# BBMiniPCB5x10.net
KiCad netlist of a schematic drawn in EAGLE
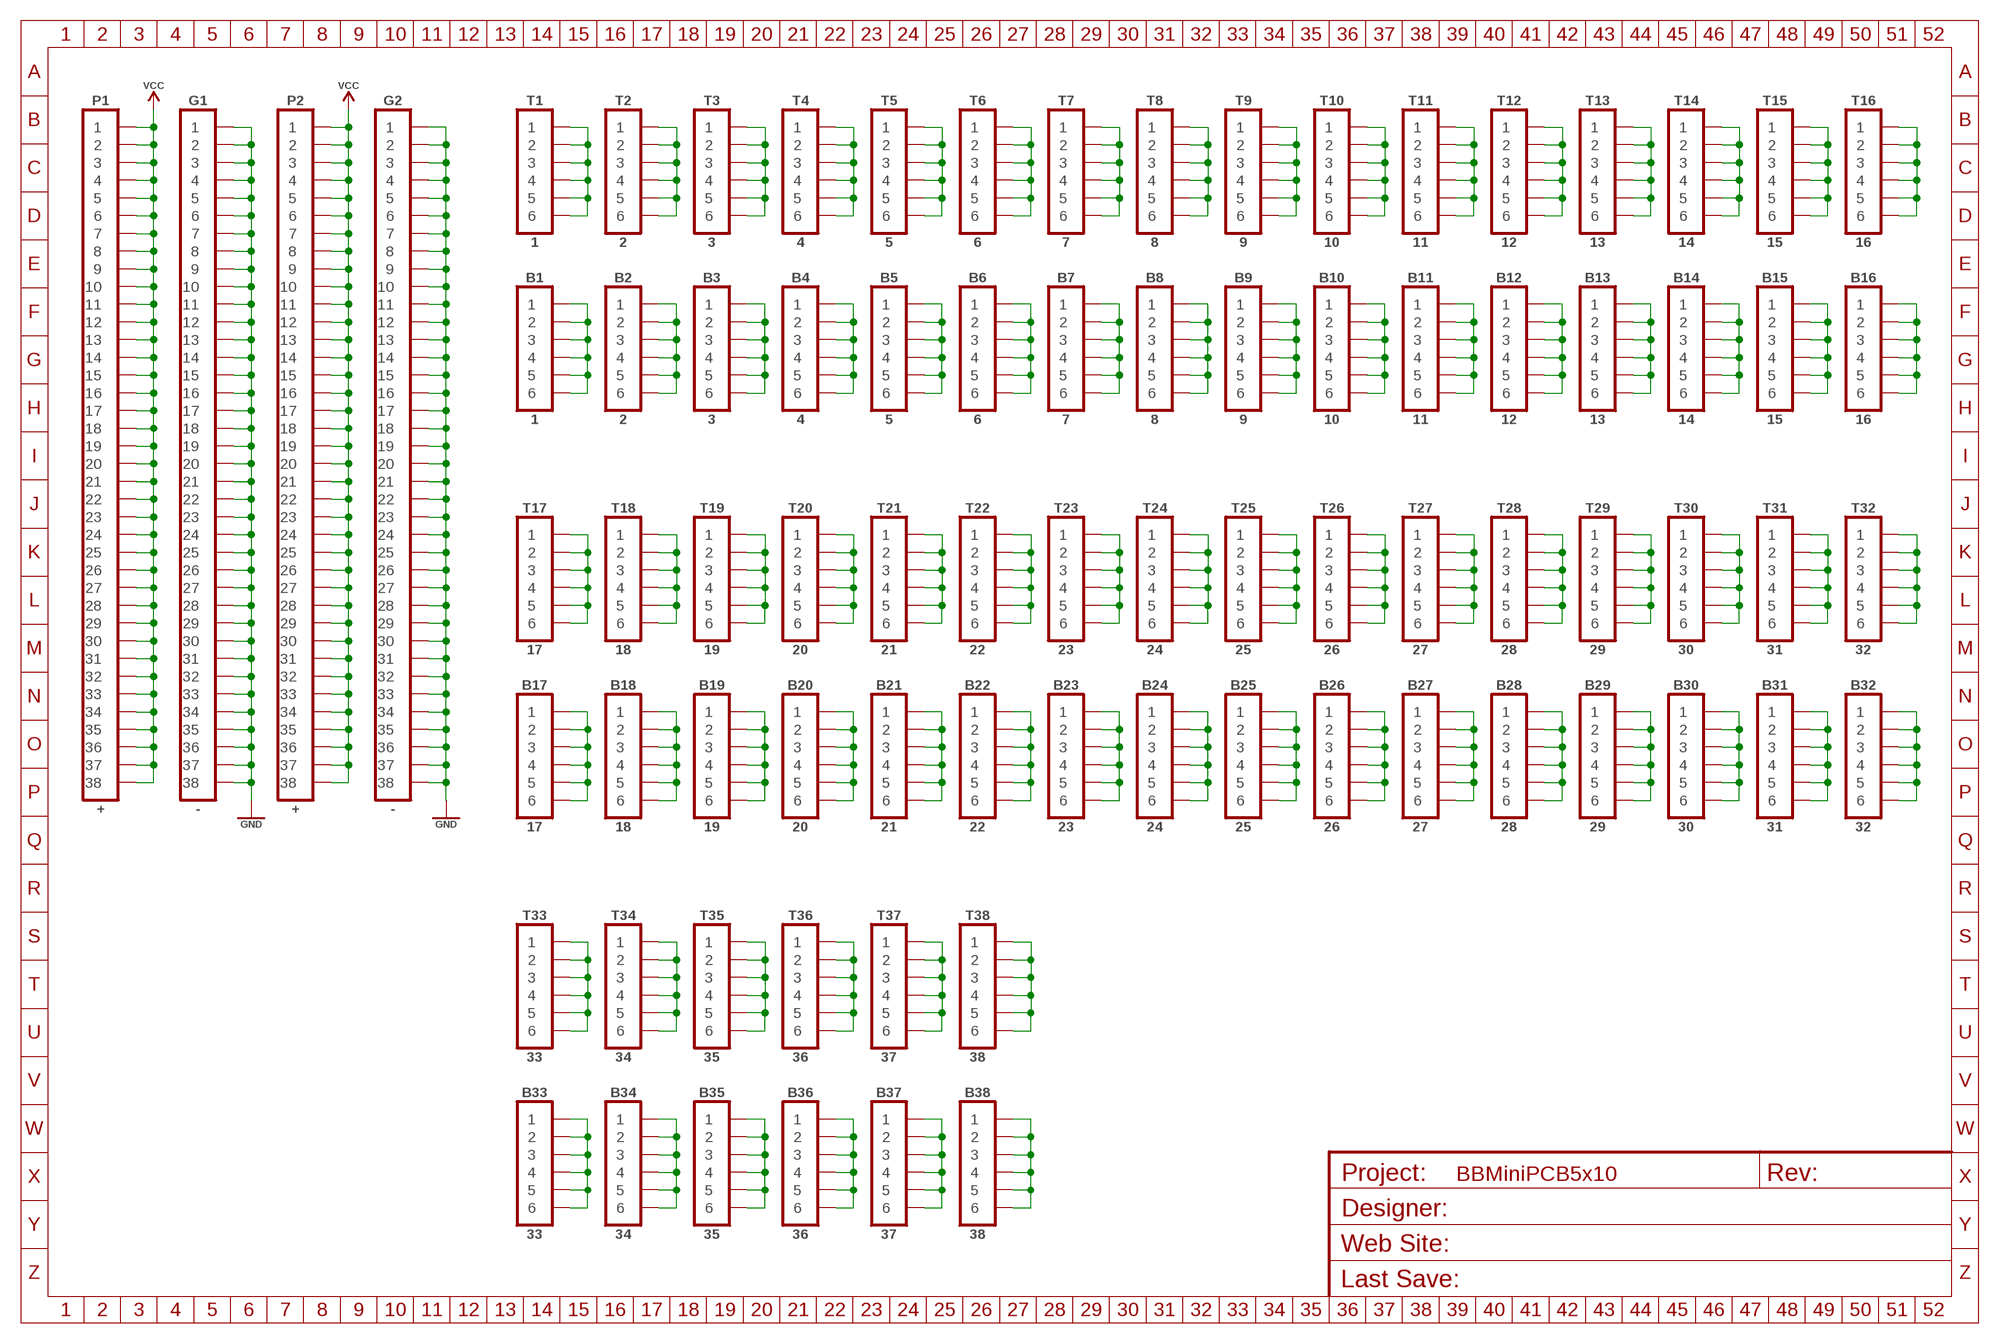
[diagram p0: schematic, sheet 1]

(export (version "E")
  (design (tool "Eeschema 10.0.6"))
  (components
    (comp (ref "B1")
      (value "1")
      (footprint "eagle-import:HDR_1X06_NOSILK")
      (libsource (lib "eagle-import") (part "HDR_1X06_NOSILK"))
    )
    (comp (ref "B2")
      (value "2")
      (footprint "eagle-import:HDR_1X06_NOSILK")
      (libsource (lib "eagle-import") (part "HDR_1X06_NOSILK"))
    )
    (comp (ref "B3")
      (value "3")
      (footprint "eagle-import:HDR_1X06_NOSILK")
      (libsource (lib "eagle-import") (part "HDR_1X06_NOSILK"))
    )
    (comp (ref "B4")
      (value "4")
      (footprint "eagle-import:HDR_1X06_NOSILK")
      (libsource (lib "eagle-import") (part "HDR_1X06_NOSILK"))
    )
    (comp (ref "B5")
      (value "5")
      (footprint "eagle-import:HDR_1X06_NOSILK")
      (libsource (lib "eagle-import") (part "HDR_1X06_NOSILK"))
    )
    (comp (ref "B6")
      (value "6")
      (footprint "eagle-import:HDR_1X06_NOSILK")
      (libsource (lib "eagle-import") (part "HDR_1X06_NOSILK"))
    )
    (comp (ref "B7")
      (value "7")
      (footprint "eagle-import:HDR_1X06_NOSILK")
      (libsource (lib "eagle-import") (part "HDR_1X06_NOSILK"))
    )
    (comp (ref "B8")
      (value "8")
      (footprint "eagle-import:HDR_1X06_NOSILK")
      (libsource (lib "eagle-import") (part "HDR_1X06_NOSILK"))
    )
    (comp (ref "B9")
      (value "9")
      (footprint "eagle-import:HDR_1X06_NOSILK")
      (libsource (lib "eagle-import") (part "HDR_1X06_NOSILK"))
    )
    (comp (ref "B10")
      (value "10")
      (footprint "eagle-import:HDR_1X06_NOSILK")
      (libsource (lib "eagle-import") (part "HDR_1X06_NOSILK"))
    )
    (comp (ref "B11")
      (value "11")
      (footprint "eagle-import:HDR_1X06_NOSILK")
      (libsource (lib "eagle-import") (part "HDR_1X06_NOSILK"))
    )
    (comp (ref "B12")
      (value "12")
      (footprint "eagle-import:HDR_1X06_NOSILK")
      (libsource (lib "eagle-import") (part "HDR_1X06_NOSILK"))
    )
    (comp (ref "B13")
      (value "13")
      (footprint "eagle-import:HDR_1X06_NOSILK")
      (libsource (lib "eagle-import") (part "HDR_1X06_NOSILK"))
    )
    (comp (ref "B14")
      (value "14")
      (footprint "eagle-import:HDR_1X06_NOSILK")
      (libsource (lib "eagle-import") (part "HDR_1X06_NOSILK"))
    )
    (comp (ref "B15")
      (value "15")
      (footprint "eagle-import:HDR_1X06_NOSILK")
      (libsource (lib "eagle-import") (part "HDR_1X06_NOSILK"))
    )
    (comp (ref "B16")
      (value "16")
      (footprint "eagle-import:HDR_1X06_NOSILK")
      (libsource (lib "eagle-import") (part "HDR_1X06_NOSILK"))
    )
    (comp (ref "B17")
      (value "17")
      (footprint "eagle-import:HDR_1X06_NOSILK")
      (libsource (lib "eagle-import") (part "HDR_1X06_NOSILK"))
    )
    (comp (ref "B18")
      (value "18")
      (footprint "eagle-import:HDR_1X06_NOSILK")
      (libsource (lib "eagle-import") (part "HDR_1X06_NOSILK"))
    )
    (comp (ref "B19")
      (value "19")
      (footprint "eagle-import:HDR_1X06_NOSILK")
      (libsource (lib "eagle-import") (part "HDR_1X06_NOSILK"))
    )
    (comp (ref "B20")
      (value "20")
      (footprint "eagle-import:HDR_1X06_NOSILK")
      (libsource (lib "eagle-import") (part "HDR_1X06_NOSILK"))
    )
    (comp (ref "B21")
      (value "21")
      (footprint "eagle-import:HDR_1X06_NOSILK")
      (libsource (lib "eagle-import") (part "HDR_1X06_NOSILK"))
    )
    (comp (ref "B22")
      (value "22")
      (footprint "eagle-import:HDR_1X06_NOSILK")
      (libsource (lib "eagle-import") (part "HDR_1X06_NOSILK"))
    )
    (comp (ref "B23")
      (value "23")
      (footprint "eagle-import:HDR_1X06_NOSILK")
      (libsource (lib "eagle-import") (part "HDR_1X06_NOSILK"))
    )
    (comp (ref "B24")
      (value "24")
      (footprint "eagle-import:HDR_1X06_NOSILK")
      (libsource (lib "eagle-import") (part "HDR_1X06_NOSILK"))
    )
    (comp (ref "B25")
      (value "25")
      (footprint "eagle-import:HDR_1X06_NOSILK")
      (libsource (lib "eagle-import") (part "HDR_1X06_NOSILK"))
    )
    (comp (ref "B26")
      (value "26")
      (footprint "eagle-import:HDR_1X06_NOSILK")
      (libsource (lib "eagle-import") (part "HDR_1X06_NOSILK"))
    )
    (comp (ref "B27")
      (value "27")
      (footprint "eagle-import:HDR_1X06_NOSILK")
      (libsource (lib "eagle-import") (part "HDR_1X06_NOSILK"))
    )
    (comp (ref "B28")
      (value "28")
      (footprint "eagle-import:HDR_1X06_NOSILK")
      (libsource (lib "eagle-import") (part "HDR_1X06_NOSILK"))
    )
    (comp (ref "B29")
      (value "29")
      (footprint "eagle-import:HDR_1X06_NOSILK")
      (libsource (lib "eagle-import") (part "HDR_1X06_NOSILK"))
    )
    (comp (ref "B30")
      (value "30")
      (footprint "eagle-import:HDR_1X06_NOSILK")
      (libsource (lib "eagle-import") (part "HDR_1X06_NOSILK"))
    )
    (comp (ref "B31")
      (value "31")
      (footprint "eagle-import:HDR_1X06_NOSILK")
      (libsource (lib "eagle-import") (part "HDR_1X06_NOSILK"))
    )
    (comp (ref "B32")
      (value "32")
      (footprint "eagle-import:HDR_1X06_NOSILK")
      (libsource (lib "eagle-import") (part "HDR_1X06_NOSILK"))
    )
    (comp (ref "B33")
      (value "33")
      (footprint "eagle-import:HDR_1X06_NOSILK")
      (libsource (lib "eagle-import") (part "HDR_1X06_NOSILK"))
    )
    (comp (ref "B34")
      (value "34")
      (footprint "eagle-import:HDR_1X06_NOSILK")
      (libsource (lib "eagle-import") (part "HDR_1X06_NOSILK"))
    )
    (comp (ref "B35")
      (value "35")
      (footprint "eagle-import:HDR_1X06_NOSILK")
      (libsource (lib "eagle-import") (part "HDR_1X06_NOSILK"))
    )
    (comp (ref "B36")
      (value "36")
      (footprint "eagle-import:HDR_1X06_NOSILK")
      (libsource (lib "eagle-import") (part "HDR_1X06_NOSILK"))
    )
    (comp (ref "B37")
      (value "37")
      (footprint "eagle-import:HDR_1X06_NOSILK")
      (libsource (lib "eagle-import") (part "HDR_1X06_NOSILK"))
    )
    (comp (ref "B38")
      (value "38")
      (footprint "eagle-import:HDR_1X06_NOSILK")
      (libsource (lib "eagle-import") (part "HDR_1X06_NOSILK"))
    )
    (comp (ref "G1")
      (value "-")
      (footprint "eagle-import:HDR_1X38_NOSILK")
      (libsource (lib "eagle-import") (part "HDR_1X38_NOSILK"))
    )
    (comp (ref "G2")
      (value "-")
      (footprint "eagle-import:HDR_1X38_NOSILK")
      (libsource (lib "eagle-import") (part "HDR_1X38_NOSILK"))
    )
    (comp (ref "P1")
      (value "+")
      (footprint "eagle-import:HDR_1X38_NOSILK")
      (libsource (lib "eagle-import") (part "HDR_1X38_NOSILK"))
    )
    (comp (ref "P2")
      (value "+")
      (footprint "eagle-import:HDR_1X38_NOSILK")
      (libsource (lib "eagle-import") (part "HDR_1X38_NOSILK"))
    )
    (comp (ref "T1")
      (value "1")
      (footprint "eagle-import:HDR_1X06_NOSILK")
      (libsource (lib "eagle-import") (part "HDR_1X06_NOSILK"))
    )
    (comp (ref "T2")
      (value "2")
      (footprint "eagle-import:HDR_1X06_NOSILK")
      (libsource (lib "eagle-import") (part "HDR_1X06_NOSILK"))
    )
    (comp (ref "T3")
      (value "3")
      (footprint "eagle-import:HDR_1X06_NOSILK")
      (libsource (lib "eagle-import") (part "HDR_1X06_NOSILK"))
    )
    (comp (ref "T4")
      (value "4")
      (footprint "eagle-import:HDR_1X06_NOSILK")
      (libsource (lib "eagle-import") (part "HDR_1X06_NOSILK"))
    )
    (comp (ref "T5")
      (value "5")
      (footprint "eagle-import:HDR_1X06_NOSILK")
      (libsource (lib "eagle-import") (part "HDR_1X06_NOSILK"))
    )
    (comp (ref "T6")
      (value "6")
      (footprint "eagle-import:HDR_1X06_NOSILK")
      (libsource (lib "eagle-import") (part "HDR_1X06_NOSILK"))
    )
    (comp (ref "T7")
      (value "7")
      (footprint "eagle-import:HDR_1X06_NOSILK")
      (libsource (lib "eagle-import") (part "HDR_1X06_NOSILK"))
    )
    (comp (ref "T8")
      (value "8")
      (footprint "eagle-import:HDR_1X06_NOSILK")
      (libsource (lib "eagle-import") (part "HDR_1X06_NOSILK"))
    )
    (comp (ref "T9")
      (value "9")
      (footprint "eagle-import:HDR_1X06_NOSILK")
      (libsource (lib "eagle-import") (part "HDR_1X06_NOSILK"))
    )
    (comp (ref "T10")
      (value "10")
      (footprint "eagle-import:HDR_1X06_NOSILK")
      (libsource (lib "eagle-import") (part "HDR_1X06_NOSILK"))
    )
    (comp (ref "T11")
      (value "11")
      (footprint "eagle-import:HDR_1X06_NOSILK")
      (libsource (lib "eagle-import") (part "HDR_1X06_NOSILK"))
    )
    (comp (ref "T12")
      (value "12")
      (footprint "eagle-import:HDR_1X06_NOSILK")
      (libsource (lib "eagle-import") (part "HDR_1X06_NOSILK"))
    )
    (comp (ref "T13")
      (value "13")
      (footprint "eagle-import:HDR_1X06_NOSILK")
      (libsource (lib "eagle-import") (part "HDR_1X06_NOSILK"))
    )
    (comp (ref "T14")
      (value "14")
      (footprint "eagle-import:HDR_1X06_NOSILK")
      (libsource (lib "eagle-import") (part "HDR_1X06_NOSILK"))
    )
    (comp (ref "T15")
      (value "15")
      (footprint "eagle-import:HDR_1X06_NOSILK")
      (libsource (lib "eagle-import") (part "HDR_1X06_NOSILK"))
    )
    (comp (ref "T16")
      (value "16")
      (footprint "eagle-import:HDR_1X06_NOSILK")
      (libsource (lib "eagle-import") (part "HDR_1X06_NOSILK"))
    )
    (comp (ref "T17")
      (value "17")
      (footprint "eagle-import:HDR_1X06_NOSILK")
      (libsource (lib "eagle-import") (part "HDR_1X06_NOSILK"))
    )
    (comp (ref "T18")
      (value "18")
      (footprint "eagle-import:HDR_1X06_NOSILK")
      (libsource (lib "eagle-import") (part "HDR_1X06_NOSILK"))
    )
    (comp (ref "T19")
      (value "19")
      (footprint "eagle-import:HDR_1X06_NOSILK")
      (libsource (lib "eagle-import") (part "HDR_1X06_NOSILK"))
    )
    (comp (ref "T20")
      (value "20")
      (footprint "eagle-import:HDR_1X06_NOSILK")
      (libsource (lib "eagle-import") (part "HDR_1X06_NOSILK"))
    )
    (comp (ref "T21")
      (value "21")
      (footprint "eagle-import:HDR_1X06_NOSILK")
      (libsource (lib "eagle-import") (part "HDR_1X06_NOSILK"))
    )
    (comp (ref "T22")
      (value "22")
      (footprint "eagle-import:HDR_1X06_NOSILK")
      (libsource (lib "eagle-import") (part "HDR_1X06_NOSILK"))
    )
    (comp (ref "T23")
      (value "23")
      (footprint "eagle-import:HDR_1X06_NOSILK")
      (libsource (lib "eagle-import") (part "HDR_1X06_NOSILK"))
    )
    (comp (ref "T24")
      (value "24")
      (footprint "eagle-import:HDR_1X06_NOSILK")
      (libsource (lib "eagle-import") (part "HDR_1X06_NOSILK"))
    )
    (comp (ref "T25")
      (value "25")
      (footprint "eagle-import:HDR_1X06_NOSILK")
      (libsource (lib "eagle-import") (part "HDR_1X06_NOSILK"))
    )
    (comp (ref "T26")
      (value "26")
      (footprint "eagle-import:HDR_1X06_NOSILK")
      (libsource (lib "eagle-import") (part "HDR_1X06_NOSILK"))
    )
    (comp (ref "T27")
      (value "27")
      (footprint "eagle-import:HDR_1X06_NOSILK")
      (libsource (lib "eagle-import") (part "HDR_1X06_NOSILK"))
    )
    (comp (ref "T28")
      (value "28")
      (footprint "eagle-import:HDR_1X06_NOSILK")
      (libsource (lib "eagle-import") (part "HDR_1X06_NOSILK"))
    )
    (comp (ref "T29")
      (value "29")
      (footprint "eagle-import:HDR_1X06_NOSILK")
      (libsource (lib "eagle-import") (part "HDR_1X06_NOSILK"))
    )
    (comp (ref "T30")
      (value "30")
      (footprint "eagle-import:HDR_1X06_NOSILK")
      (libsource (lib "eagle-import") (part "HDR_1X06_NOSILK"))
    )
    (comp (ref "T31")
      (value "31")
      (footprint "eagle-import:HDR_1X06_NOSILK")
      (libsource (lib "eagle-import") (part "HDR_1X06_NOSILK"))
    )
    (comp (ref "T32")
      (value "32")
      (footprint "eagle-import:HDR_1X06_NOSILK")
      (libsource (lib "eagle-import") (part "HDR_1X06_NOSILK"))
    )
    (comp (ref "T33")
      (value "33")
      (footprint "eagle-import:HDR_1X06_NOSILK")
      (libsource (lib "eagle-import") (part "HDR_1X06_NOSILK"))
    )
    (comp (ref "T34")
      (value "34")
      (footprint "eagle-import:HDR_1X06_NOSILK")
      (libsource (lib "eagle-import") (part "HDR_1X06_NOSILK"))
    )
    (comp (ref "T35")
      (value "35")
      (footprint "eagle-import:HDR_1X06_NOSILK")
      (libsource (lib "eagle-import") (part "HDR_1X06_NOSILK"))
    )
    (comp (ref "T36")
      (value "36")
      (footprint "eagle-import:HDR_1X06_NOSILK")
      (libsource (lib "eagle-import") (part "HDR_1X06_NOSILK"))
    )
    (comp (ref "T37")
      (value "37")
      (footprint "eagle-import:HDR_1X06_NOSILK")
      (libsource (lib "eagle-import") (part "HDR_1X06_NOSILK"))
    )
    (comp (ref "T38")
      (value "38")
      (footprint "eagle-import:HDR_1X06_NOSILK")
      (libsource (lib "eagle-import") (part "HDR_1X06_NOSILK"))
    )
  )
  (nets
    (net (code "1") (name "GND") (class "Default")
      (node (ref "G1") (pin "1") (pinfunction "1_1") (pintype "passive"))
      (node (ref "G1") (pin "10") (pinfunction "10_10") (pintype "passive"))
      (node (ref "G1") (pin "11") (pinfunction "11_11") (pintype "passive"))
      (node (ref "G1") (pin "12") (pinfunction "12_12") (pintype "passive"))
      (node (ref "G1") (pin "13") (pinfunction "13_13") (pintype "passive"))
      (node (ref "G1") (pin "14") (pinfunction "14_14") (pintype "passive"))
      (node (ref "G1") (pin "15") (pinfunction "15_15") (pintype "passive"))
      (node (ref "G1") (pin "16") (pinfunction "16_16") (pintype "passive"))
      (node (ref "G1") (pin "17") (pinfunction "17_17") (pintype "passive"))
      (node (ref "G1") (pin "18") (pinfunction "18_18") (pintype "passive"))
      (node (ref "G1") (pin "19") (pinfunction "19_19") (pintype "passive"))
      (node (ref "G1") (pin "2") (pinfunction "2_2") (pintype "passive"))
      (node (ref "G1") (pin "20") (pinfunction "20_20") (pintype "passive"))
      (node (ref "G1") (pin "21") (pinfunction "21_21") (pintype "passive"))
      (node (ref "G1") (pin "22") (pinfunction "22_22") (pintype "passive"))
      (node (ref "G1") (pin "23") (pinfunction "23_23") (pintype "passive"))
      (node (ref "G1") (pin "24") (pinfunction "24_24") (pintype "passive"))
      (node (ref "G1") (pin "25") (pinfunction "25_25") (pintype "passive"))
      (node (ref "G1") (pin "26") (pinfunction "26_26") (pintype "passive"))
      (node (ref "G1") (pin "27") (pinfunction "27_27") (pintype "passive"))
      (node (ref "G1") (pin "28") (pinfunction "28_28") (pintype "passive"))
      (node (ref "G1") (pin "29") (pinfunction "29_29") (pintype "passive"))
      (node (ref "G1") (pin "3") (pinfunction "3_3") (pintype "passive"))
      (node (ref "G1") (pin "30") (pinfunction "30_30") (pintype "passive"))
      (node (ref "G1") (pin "31") (pinfunction "31_31") (pintype "passive"))
      (node (ref "G1") (pin "32") (pinfunction "32_32") (pintype "passive"))
      (node (ref "G1") (pin "33") (pinfunction "33_33") (pintype "passive"))
      (node (ref "G1") (pin "34") (pinfunction "34_34") (pintype "passive"))
      (node (ref "G1") (pin "35") (pinfunction "35_35") (pintype "passive"))
      (node (ref "G1") (pin "36") (pinfunction "36_36") (pintype "passive"))
      (node (ref "G1") (pin "37") (pinfunction "37_37") (pintype "passive"))
      (node (ref "G1") (pin "38") (pinfunction "38_38") (pintype "passive"))
      (node (ref "G1") (pin "4") (pinfunction "4_4") (pintype "passive"))
      (node (ref "G1") (pin "5") (pinfunction "5_5") (pintype "passive"))
      (node (ref "G1") (pin "6") (pinfunction "6_6") (pintype "passive"))
      (node (ref "G1") (pin "7") (pinfunction "7_7") (pintype "passive"))
      (node (ref "G1") (pin "8") (pinfunction "8_8") (pintype "passive"))
      (node (ref "G1") (pin "9") (pinfunction "9_9") (pintype "passive"))
      (node (ref "G2") (pin "1") (pinfunction "1_1") (pintype "passive"))
      (node (ref "G2") (pin "10") (pinfunction "10_10") (pintype "passive"))
      (node (ref "G2") (pin "11") (pinfunction "11_11") (pintype "passive"))
      (node (ref "G2") (pin "12") (pinfunction "12_12") (pintype "passive"))
      (node (ref "G2") (pin "13") (pinfunction "13_13") (pintype "passive"))
      (node (ref "G2") (pin "14") (pinfunction "14_14") (pintype "passive"))
      (node (ref "G2") (pin "15") (pinfunction "15_15") (pintype "passive"))
      (node (ref "G2") (pin "16") (pinfunction "16_16") (pintype "passive"))
      (node (ref "G2") (pin "17") (pinfunction "17_17") (pintype "passive"))
      (node (ref "G2") (pin "18") (pinfunction "18_18") (pintype "passive"))
      (node (ref "G2") (pin "19") (pinfunction "19_19") (pintype "passive"))
      (node (ref "G2") (pin "2") (pinfunction "2_2") (pintype "passive"))
      (node (ref "G2") (pin "20") (pinfunction "20_20") (pintype "passive"))
      (node (ref "G2") (pin "21") (pinfunction "21_21") (pintype "passive"))
      (node (ref "G2") (pin "22") (pinfunction "22_22") (pintype "passive"))
      (node (ref "G2") (pin "23") (pinfunction "23_23") (pintype "passive"))
      (node (ref "G2") (pin "24") (pinfunction "24_24") (pintype "passive"))
      (node (ref "G2") (pin "25") (pinfunction "25_25") (pintype "passive"))
      (node (ref "G2") (pin "26") (pinfunction "26_26") (pintype "passive"))
      (node (ref "G2") (pin "27") (pinfunction "27_27") (pintype "passive"))
      (node (ref "G2") (pin "28") (pinfunction "28_28") (pintype "passive"))
      (node (ref "G2") (pin "29") (pinfunction "29_29") (pintype "passive"))
      (node (ref "G2") (pin "3") (pinfunction "3_3") (pintype "passive"))
      (node (ref "G2") (pin "30") (pinfunction "30_30") (pintype "passive"))
      (node (ref "G2") (pin "31") (pinfunction "31_31") (pintype "passive"))
      (node (ref "G2") (pin "32") (pinfunction "32_32") (pintype "passive"))
      (node (ref "G2") (pin "33") (pinfunction "33_33") (pintype "passive"))
      (node (ref "G2") (pin "34") (pinfunction "34_34") (pintype "passive"))
      (node (ref "G2") (pin "35") (pinfunction "35_35") (pintype "passive"))
      (node (ref "G2") (pin "36") (pinfunction "36_36") (pintype "passive"))
      (node (ref "G2") (pin "37") (pinfunction "37_37") (pintype "passive"))
      (node (ref "G2") (pin "38") (pinfunction "38_38") (pintype "passive"))
      (node (ref "G2") (pin "4") (pinfunction "4_4") (pintype "passive"))
      (node (ref "G2") (pin "5") (pinfunction "5_5") (pintype "passive"))
      (node (ref "G2") (pin "6") (pinfunction "6_6") (pintype "passive"))
      (node (ref "G2") (pin "7") (pinfunction "7_7") (pintype "passive"))
      (node (ref "G2") (pin "8") (pinfunction "8_8") (pintype "passive"))
      (node (ref "G2") (pin "9") (pinfunction "9_9") (pintype "passive"))
    )
    (net (code "2") (name "Net-(B1-Pad1)") (class "Default")
      (node (ref "B1") (pin "1") (pinfunction "1_1") (pintype "passive"))
      (node (ref "B1") (pin "2") (pinfunction "2_2") (pintype "passive"))
      (node (ref "B1") (pin "3") (pinfunction "3_3") (pintype "passive"))
      (node (ref "B1") (pin "4") (pinfunction "4_4") (pintype "passive"))
      (node (ref "B1") (pin "5") (pinfunction "5_5") (pintype "passive"))
      (node (ref "B1") (pin "6") (pinfunction "6_6") (pintype "passive"))
    )
    (net (code "3") (name "Net-(B2-Pad1)") (class "Default")
      (node (ref "B2") (pin "1") (pinfunction "1_1") (pintype "passive"))
      (node (ref "B2") (pin "2") (pinfunction "2_2") (pintype "passive"))
      (node (ref "B2") (pin "3") (pinfunction "3_3") (pintype "passive"))
      (node (ref "B2") (pin "4") (pinfunction "4_4") (pintype "passive"))
      (node (ref "B2") (pin "5") (pinfunction "5_5") (pintype "passive"))
      (node (ref "B2") (pin "6") (pinfunction "6_6") (pintype "passive"))
    )
    (net (code "4") (name "Net-(B3-Pad1)") (class "Default")
      (node (ref "B3") (pin "1") (pinfunction "1_1") (pintype "passive"))
      (node (ref "B3") (pin "2") (pinfunction "2_2") (pintype "passive"))
      (node (ref "B3") (pin "3") (pinfunction "3_3") (pintype "passive"))
      (node (ref "B3") (pin "4") (pinfunction "4_4") (pintype "passive"))
      (node (ref "B3") (pin "5") (pinfunction "5_5") (pintype "passive"))
      (node (ref "B3") (pin "6") (pinfunction "6_6") (pintype "passive"))
    )
    (net (code "5") (name "Net-(B4-Pad1)") (class "Default")
      (node (ref "B4") (pin "1") (pinfunction "1_1") (pintype "passive"))
      (node (ref "B4") (pin "2") (pinfunction "2_2") (pintype "passive"))
      (node (ref "B4") (pin "3") (pinfunction "3_3") (pintype "passive"))
      (node (ref "B4") (pin "4") (pinfunction "4_4") (pintype "passive"))
      (node (ref "B4") (pin "5") (pinfunction "5_5") (pintype "passive"))
      (node (ref "B4") (pin "6") (pinfunction "6_6") (pintype "passive"))
    )
    (net (code "6") (name "Net-(B5-Pad1)") (class "Default")
      (node (ref "B5") (pin "1") (pinfunction "1_1") (pintype "passive"))
      (node (ref "B5") (pin "2") (pinfunction "2_2") (pintype "passive"))
      (node (ref "B5") (pin "3") (pinfunction "3_3") (pintype "passive"))
      (node (ref "B5") (pin "4") (pinfunction "4_4") (pintype "passive"))
      (node (ref "B5") (pin "5") (pinfunction "5_5") (pintype "passive"))
      (node (ref "B5") (pin "6") (pinfunction "6_6") (pintype "passive"))
    )
    (net (code "7") (name "Net-(B6-Pad1)") (class "Default")
      (node (ref "B6") (pin "1") (pinfunction "1_1") (pintype "passive"))
      (node (ref "B6") (pin "2") (pinfunction "2_2") (pintype "passive"))
      (node (ref "B6") (pin "3") (pinfunction "3_3") (pintype "passive"))
      (node (ref "B6") (pin "4") (pinfunction "4_4") (pintype "passive"))
      (node (ref "B6") (pin "5") (pinfunction "5_5") (pintype "passive"))
      (node (ref "B6") (pin "6") (pinfunction "6_6") (pintype "passive"))
    )
    (net (code "8") (name "Net-(B7-Pad1)") (class "Default")
      (node (ref "B7") (pin "1") (pinfunction "1_1") (pintype "passive"))
      (node (ref "B7") (pin "2") (pinfunction "2_2") (pintype "passive"))
      (node (ref "B7") (pin "3") (pinfunction "3_3") (pintype "passive"))
      (node (ref "B7") (pin "4") (pinfunction "4_4") (pintype "passive"))
      (node (ref "B7") (pin "5") (pinfunction "5_5") (pintype "passive"))
      (node (ref "B7") (pin "6") (pinfunction "6_6") (pintype "passive"))
    )
    (net (code "9") (name "Net-(B8-Pad1)") (class "Default")
      (node (ref "B8") (pin "1") (pinfunction "1_1") (pintype "passive"))
      (node (ref "B8") (pin "2") (pinfunction "2_2") (pintype "passive"))
      (node (ref "B8") (pin "3") (pinfunction "3_3") (pintype "passive"))
      (node (ref "B8") (pin "4") (pinfunction "4_4") (pintype "passive"))
      (node (ref "B8") (pin "5") (pinfunction "5_5") (pintype "passive"))
      (node (ref "B8") (pin "6") (pinfunction "6_6") (pintype "passive"))
    )
    (net (code "10") (name "Net-(B9-Pad1)") (class "Default")
      (node (ref "B9") (pin "1") (pinfunction "1_1") (pintype "passive"))
      (node (ref "B9") (pin "2") (pinfunction "2_2") (pintype "passive"))
      (node (ref "B9") (pin "3") (pinfunction "3_3") (pintype "passive"))
      (node (ref "B9") (pin "4") (pinfunction "4_4") (pintype "passive"))
      (node (ref "B9") (pin "5") (pinfunction "5_5") (pintype "passive"))
      (node (ref "B9") (pin "6") (pinfunction "6_6") (pintype "passive"))
    )
    (net (code "11") (name "Net-(B10-Pad1)") (class "Default")
      (node (ref "B10") (pin "1") (pinfunction "1_1") (pintype "passive"))
      (node (ref "B10") (pin "2") (pinfunction "2_2") (pintype "passive"))
      (node (ref "B10") (pin "3") (pinfunction "3_3") (pintype "passive"))
      (node (ref "B10") (pin "4") (pinfunction "4_4") (pintype "passive"))
      (node (ref "B10") (pin "5") (pinfunction "5_5") (pintype "passive"))
      (node (ref "B10") (pin "6") (pinfunction "6_6") (pintype "passive"))
    )
    (net (code "12") (name "Net-(B11-Pad1)") (class "Default")
      (node (ref "B11") (pin "1") (pinfunction "1_1") (pintype "passive"))
      (node (ref "B11") (pin "2") (pinfunction "2_2") (pintype "passive"))
      (node (ref "B11") (pin "3") (pinfunction "3_3") (pintype "passive"))
      (node (ref "B11") (pin "4") (pinfunction "4_4") (pintype "passive"))
      (node (ref "B11") (pin "5") (pinfunction "5_5") (pintype "passive"))
      (node (ref "B11") (pin "6") (pinfunction "6_6") (pintype "passive"))
    )
    (net (code "13") (name "Net-(B12-Pad1)") (class "Default")
      (node (ref "B12") (pin "1") (pinfunction "1_1") (pintype "passive"))
      (node (ref "B12") (pin "2") (pinfunction "2_2") (pintype "passive"))
      (node (ref "B12") (pin "3") (pinfunction "3_3") (pintype "passive"))
      (node (ref "B12") (pin "4") (pinfunction "4_4") (pintype "passive"))
      (node (ref "B12") (pin "5") (pinfunction "5_5") (pintype "passive"))
      (node (ref "B12") (pin "6") (pinfunction "6_6") (pintype "passive"))
    )
    (net (code "14") (name "Net-(B13-Pad1)") (class "Default")
      (node (ref "B13") (pin "1") (pinfunction "1_1") (pintype "passive"))
      (node (ref "B13") (pin "2") (pinfunction "2_2") (pintype "passive"))
      (node (ref "B13") (pin "3") (pinfunction "3_3") (pintype "passive"))
      (node (ref "B13") (pin "4") (pinfunction "4_4") (pintype "passive"))
      (node (ref "B13") (pin "5") (pinfunction "5_5") (pintype "passive"))
      (node (ref "B13") (pin "6") (pinfunction "6_6") (pintype "passive"))
    )
    (net (code "15") (name "Net-(B14-Pad1)") (class "Default")
      (node (ref "B14") (pin "1") (pinfunction "1_1") (pintype "passive"))
      (node (ref "B14") (pin "2") (pinfunction "2_2") (pintype "passive"))
      (node (ref "B14") (pin "3") (pinfunction "3_3") (pintype "passive"))
      (node (ref "B14") (pin "4") (pinfunction "4_4") (pintype "passive"))
      (node (ref "B14") (pin "5") (pinfunction "5_5") (pintype "passive"))
      (node (ref "B14") (pin "6") (pinfunction "6_6") (pintype "passive"))
    )
    (net (code "16") (name "Net-(B15-Pad1)") (class "Default")
      (node (ref "B15") (pin "1") (pinfunction "1_1") (pintype "passive"))
      (node (ref "B15") (pin "2") (pinfunction "2_2") (pintype "passive"))
      (node (ref "B15") (pin "3") (pinfunction "3_3") (pintype "passive"))
      (node (ref "B15") (pin "4") (pinfunction "4_4") (pintype "passive"))
      (node (ref "B15") (pin "5") (pinfunction "5_5") (pintype "passive"))
      (node (ref "B15") (pin "6") (pinfunction "6_6") (pintype "passive"))
    )
    (net (code "17") (name "Net-(B16-Pad1)") (class "Default")
      (node (ref "B16") (pin "1") (pinfunction "1_1") (pintype "passive"))
      (node (ref "B16") (pin "2") (pinfunction "2_2") (pintype "passive"))
      (node (ref "B16") (pin "3") (pinfunction "3_3") (pintype "passive"))
      (node (ref "B16") (pin "4") (pinfunction "4_4") (pintype "passive"))
      (node (ref "B16") (pin "5") (pinfunction "5_5") (pintype "passive"))
      (node (ref "B16") (pin "6") (pinfunction "6_6") (pintype "passive"))
    )
    (net (code "18") (name "Net-(B17-Pad1)") (class "Default")
      (node (ref "B17") (pin "1") (pinfunction "1_1") (pintype "passive"))
      (node (ref "B17") (pin "2") (pinfunction "2_2") (pintype "passive"))
      (node (ref "B17") (pin "3") (pinfunction "3_3") (pintype "passive"))
      (node (ref "B17") (pin "4") (pinfunction "4_4") (pintype "passive"))
      (node (ref "B17") (pin "5") (pinfunction "5_5") (pintype "passive"))
      (node (ref "B17") (pin "6") (pinfunction "6_6") (pintype "passive"))
    )
    (net (code "19") (name "Net-(B18-Pad1)") (class "Default")
      (node (ref "B18") (pin "1") (pinfunction "1_1") (pintype "passive"))
      (node (ref "B18") (pin "2") (pinfunction "2_2") (pintype "passive"))
      (node (ref "B18") (pin "3") (pinfunction "3_3") (pintype "passive"))
      (node (ref "B18") (pin "4") (pinfunction "4_4") (pintype "passive"))
      (node (ref "B18") (pin "5") (pinfunction "5_5") (pintype "passive"))
      (node (ref "B18") (pin "6") (pinfunction "6_6") (pintype "passive"))
    )
    (net (code "20") (name "Net-(B19-Pad1)") (class "Default")
      (node (ref "B19") (pin "1") (pinfunction "1_1") (pintype "passive"))
      (node (ref "B19") (pin "2") (pinfunction "2_2") (pintype "passive"))
      (node (ref "B19") (pin "3") (pinfunction "3_3") (pintype "passive"))
      (node (ref "B19") (pin "4") (pinfunction "4_4") (pintype "passive"))
      (node (ref "B19") (pin "5") (pinfunction "5_5") (pintype "passive"))
      (node (ref "B19") (pin "6") (pinfunction "6_6") (pintype "passive"))
    )
    (net (code "21") (name "Net-(B20-Pad1)") (class "Default")
      (node (ref "B20") (pin "1") (pinfunction "1_1") (pintype "passive"))
      (node (ref "B20") (pin "2") (pinfunction "2_2") (pintype "passive"))
      (node (ref "B20") (pin "3") (pinfunction "3_3") (pintype "passive"))
      (node (ref "B20") (pin "4") (pinfunction "4_4") (pintype "passive"))
      (node (ref "B20") (pin "5") (pinfunction "5_5") (pintype "passive"))
      (node (ref "B20") (pin "6") (pinfunction "6_6") (pintype "passive"))
    )
    (net (code "22") (name "Net-(B21-Pad1)") (class "Default")
      (node (ref "B21") (pin "1") (pinfunction "1_1") (pintype "passive"))
      (node (ref "B21") (pin "2") (pinfunction "2_2") (pintype "passive"))
      (node (ref "B21") (pin "3") (pinfunction "3_3") (pintype "passive"))
      (node (ref "B21") (pin "4") (pinfunction "4_4") (pintype "passive"))
      (node (ref "B21") (pin "5") (pinfunction "5_5") (pintype "passive"))
      (node (ref "B21") (pin "6") (pinfunction "6_6") (pintype "passive"))
    )
    (net (code "23") (name "Net-(B22-Pad1)") (class "Default")
      (node (ref "B22") (pin "1") (pinfunction "1_1") (pintype "passive"))
      (node (ref "B22") (pin "2") (pinfunction "2_2") (pintype "passive"))
      (node (ref "B22") (pin "3") (pinfunction "3_3") (pintype "passive"))
      (node (ref "B22") (pin "4") (pinfunction "4_4") (pintype "passive"))
      (node (ref "B22") (pin "5") (pinfunction "5_5") (pintype "passive"))
      (node (ref "B22") (pin "6") (pinfunction "6_6") (pintype "passive"))
    )
    (net (code "24") (name "Net-(B23-Pad1)") (class "Default")
      (node (ref "B23") (pin "1") (pinfunction "1_1") (pintype "passive"))
      (node (ref "B23") (pin "2") (pinfunction "2_2") (pintype "passive"))
      (node (ref "B23") (pin "3") (pinfunction "3_3") (pintype "passive"))
      (node (ref "B23") (pin "4") (pinfunction "4_4") (pintype "passive"))
      (node (ref "B23") (pin "5") (pinfunction "5_5") (pintype "passive"))
      (node (ref "B23") (pin "6") (pinfunction "6_6") (pintype "passive"))
    )
    (net (code "25") (name "Net-(B24-Pad1)") (class "Default")
      (node (ref "B24") (pin "1") (pinfunction "1_1") (pintype "passive"))
      (node (ref "B24") (pin "2") (pinfunction "2_2") (pintype "passive"))
      (node (ref "B24") (pin "3") (pinfunction "3_3") (pintype "passive"))
      (node (ref "B24") (pin "4") (pinfunction "4_4") (pintype "passive"))
      (node (ref "B24") (pin "5") (pinfunction "5_5") (pintype "passive"))
      (node (ref "B24") (pin "6") (pinfunction "6_6") (pintype "passive"))
    )
    (net (code "26") (name "Net-(B25-Pad1)") (class "Default")
      (node (ref "B25") (pin "1") (pinfunction "1_1") (pintype "passive"))
      (node (ref "B25") (pin "2") (pinfunction "2_2") (pintype "passive"))
      (node (ref "B25") (pin "3") (pinfunction "3_3") (pintype "passive"))
      (node (ref "B25") (pin "4") (pinfunction "4_4") (pintype "passive"))
      (node (ref "B25") (pin "5") (pinfunction "5_5") (pintype "passive"))
      (node (ref "B25") (pin "6") (pinfunction "6_6") (pintype "passive"))
    )
    (net (code "27") (name "Net-(B26-Pad1)") (class "Default")
      (node (ref "B26") (pin "1") (pinfunction "1_1") (pintype "passive"))
      (node (ref "B26") (pin "2") (pinfunction "2_2") (pintype "passive"))
      (node (ref "B26") (pin "3") (pinfunction "3_3") (pintype "passive"))
      (node (ref "B26") (pin "4") (pinfunction "4_4") (pintype "passive"))
      (node (ref "B26") (pin "5") (pinfunction "5_5") (pintype "passive"))
      (node (ref "B26") (pin "6") (pinfunction "6_6") (pintype "passive"))
    )
    (net (code "28") (name "Net-(B27-Pad1)") (class "Default")
      (node (ref "B27") (pin "1") (pinfunction "1_1") (pintype "passive"))
      (node (ref "B27") (pin "2") (pinfunction "2_2") (pintype "passive"))
      (node (ref "B27") (pin "3") (pinfunction "3_3") (pintype "passive"))
      (node (ref "B27") (pin "4") (pinfunction "4_4") (pintype "passive"))
      (node (ref "B27") (pin "5") (pinfunction "5_5") (pintype "passive"))
      (node (ref "B27") (pin "6") (pinfunction "6_6") (pintype "passive"))
    )
    (net (code "29") (name "Net-(B28-Pad1)") (class "Default")
      (node (ref "B28") (pin "1") (pinfunction "1_1") (pintype "passive"))
      (node (ref "B28") (pin "2") (pinfunction "2_2") (pintype "passive"))
      (node (ref "B28") (pin "3") (pinfunction "3_3") (pintype "passive"))
      (node (ref "B28") (pin "4") (pinfunction "4_4") (pintype "passive"))
      (node (ref "B28") (pin "5") (pinfunction "5_5") (pintype "passive"))
      (node (ref "B28") (pin "6") (pinfunction "6_6") (pintype "passive"))
    )
    (net (code "30") (name "Net-(B29-Pad1)") (class "Default")
      (node (ref "B29") (pin "1") (pinfunction "1_1") (pintype "passive"))
      (node (ref "B29") (pin "2") (pinfunction "2_2") (pintype "passive"))
      (node (ref "B29") (pin "3") (pinfunction "3_3") (pintype "passive"))
      (node (ref "B29") (pin "4") (pinfunction "4_4") (pintype "passive"))
      (node (ref "B29") (pin "5") (pinfunction "5_5") (pintype "passive"))
      (node (ref "B29") (pin "6") (pinfunction "6_6") (pintype "passive"))
    )
    (net (code "31") (name "Net-(B30-Pad1)") (class "Default")
      (node (ref "B30") (pin "1") (pinfunction "1_1") (pintype "passive"))
      (node (ref "B30") (pin "2") (pinfunction "2_2") (pintype "passive"))
      (node (ref "B30") (pin "3") (pinfunction "3_3") (pintype "passive"))
      (node (ref "B30") (pin "4") (pinfunction "4_4") (pintype "passive"))
      (node (ref "B30") (pin "5") (pinfunction "5_5") (pintype "passive"))
      (node (ref "B30") (pin "6") (pinfunction "6_6") (pintype "passive"))
    )
    (net (code "32") (name "Net-(B31-Pad1)") (class "Default")
      (node (ref "B31") (pin "1") (pinfunction "1_1") (pintype "passive"))
      (node (ref "B31") (pin "2") (pinfunction "2_2") (pintype "passive"))
      (node (ref "B31") (pin "3") (pinfunction "3_3") (pintype "passive"))
      (node (ref "B31") (pin "4") (pinfunction "4_4") (pintype "passive"))
      (node (ref "B31") (pin "5") (pinfunction "5_5") (pintype "passive"))
      (node (ref "B31") (pin "6") (pinfunction "6_6") (pintype "passive"))
    )
    (net (code "33") (name "Net-(B32-Pad1)") (class "Default")
      (node (ref "B32") (pin "1") (pinfunction "1_1") (pintype "passive"))
      (node (ref "B32") (pin "2") (pinfunction "2_2") (pintype "passive"))
      (node (ref "B32") (pin "3") (pinfunction "3_3") (pintype "passive"))
      (node (ref "B32") (pin "4") (pinfunction "4_4") (pintype "passive"))
      (node (ref "B32") (pin "5") (pinfunction "5_5") (pintype "passive"))
      (node (ref "B32") (pin "6") (pinfunction "6_6") (pintype "passive"))
    )
    (net (code "34") (name "Net-(B33-Pad1)") (class "Default")
      (node (ref "B33") (pin "1") (pinfunction "1_1") (pintype "passive"))
      (node (ref "B33") (pin "2") (pinfunction "2_2") (pintype "passive"))
      (node (ref "B33") (pin "3") (pinfunction "3_3") (pintype "passive"))
      (node (ref "B33") (pin "4") (pinfunction "4_4") (pintype "passive"))
      (node (ref "B33") (pin "5") (pinfunction "5_5") (pintype "passive"))
      (node (ref "B33") (pin "6") (pinfunction "6_6") (pintype "passive"))
    )
    (net (code "35") (name "Net-(B34-Pad1)") (class "Default")
      (node (ref "B34") (pin "1") (pinfunction "1_1") (pintype "passive"))
      (node (ref "B34") (pin "2") (pinfunction "2_2") (pintype "passive"))
      (node (ref "B34") (pin "3") (pinfunction "3_3") (pintype "passive"))
      (node (ref "B34") (pin "4") (pinfunction "4_4") (pintype "passive"))
      (node (ref "B34") (pin "5") (pinfunction "5_5") (pintype "passive"))
      (node (ref "B34") (pin "6") (pinfunction "6_6") (pintype "passive"))
    )
    (net (code "36") (name "Net-(B35-Pad1)") (class "Default")
      (node (ref "B35") (pin "1") (pinfunction "1_1") (pintype "passive"))
      (node (ref "B35") (pin "2") (pinfunction "2_2") (pintype "passive"))
      (node (ref "B35") (pin "3") (pinfunction "3_3") (pintype "passive"))
      (node (ref "B35") (pin "4") (pinfunction "4_4") (pintype "passive"))
      (node (ref "B35") (pin "5") (pinfunction "5_5") (pintype "passive"))
      (node (ref "B35") (pin "6") (pinfunction "6_6") (pintype "passive"))
    )
    (net (code "37") (name "Net-(B36-Pad1)") (class "Default")
      (node (ref "B36") (pin "1") (pinfunction "1_1") (pintype "passive"))
      (node (ref "B36") (pin "2") (pinfunction "2_2") (pintype "passive"))
      (node (ref "B36") (pin "3") (pinfunction "3_3") (pintype "passive"))
      (node (ref "B36") (pin "4") (pinfunction "4_4") (pintype "passive"))
      (node (ref "B36") (pin "5") (pinfunction "5_5") (pintype "passive"))
      (node (ref "B36") (pin "6") (pinfunction "6_6") (pintype "passive"))
    )
    (net (code "38") (name "Net-(B37-Pad1)") (class "Default")
      (node (ref "B37") (pin "1") (pinfunction "1_1") (pintype "passive"))
      (node (ref "B37") (pin "2") (pinfunction "2_2") (pintype "passive"))
      (node (ref "B37") (pin "3") (pinfunction "3_3") (pintype "passive"))
      (node (ref "B37") (pin "4") (pinfunction "4_4") (pintype "passive"))
      (node (ref "B37") (pin "5") (pinfunction "5_5") (pintype "passive"))
      (node (ref "B37") (pin "6") (pinfunction "6_6") (pintype "passive"))
    )
    (net (code "39") (name "Net-(B38-Pad1)") (class "Default")
      (node (ref "B38") (pin "1") (pinfunction "1_1") (pintype "passive"))
      (node (ref "B38") (pin "2") (pinfunction "2_2") (pintype "passive"))
      (node (ref "B38") (pin "3") (pinfunction "3_3") (pintype "passive"))
      (node (ref "B38") (pin "4") (pinfunction "4_4") (pintype "passive"))
      (node (ref "B38") (pin "5") (pinfunction "5_5") (pintype "passive"))
      (node (ref "B38") (pin "6") (pinfunction "6_6") (pintype "passive"))
    )
    (net (code "40") (name "Net-(T1-Pad1)") (class "Default")
      (node (ref "T1") (pin "1") (pinfunction "1_1") (pintype "passive"))
      (node (ref "T1") (pin "2") (pinfunction "2_2") (pintype "passive"))
      (node (ref "T1") (pin "3") (pinfunction "3_3") (pintype "passive"))
      (node (ref "T1") (pin "4") (pinfunction "4_4") (pintype "passive"))
      (node (ref "T1") (pin "5") (pinfunction "5_5") (pintype "passive"))
      (node (ref "T1") (pin "6") (pinfunction "6_6") (pintype "passive"))
    )
    (net (code "41") (name "Net-(T2-Pad1)") (class "Default")
      (node (ref "T2") (pin "1") (pinfunction "1_1") (pintype "passive"))
      (node (ref "T2") (pin "2") (pinfunction "2_2") (pintype "passive"))
      (node (ref "T2") (pin "3") (pinfunction "3_3") (pintype "passive"))
      (node (ref "T2") (pin "4") (pinfunction "4_4") (pintype "passive"))
      (node (ref "T2") (pin "5") (pinfunction "5_5") (pintype "passive"))
      (node (ref "T2") (pin "6") (pinfunction "6_6") (pintype "passive"))
    )
    (net (code "42") (name "Net-(T3-Pad1)") (class "Default")
      (node (ref "T3") (pin "1") (pinfunction "1_1") (pintype "passive"))
      (node (ref "T3") (pin "2") (pinfunction "2_2") (pintype "passive"))
      (node (ref "T3") (pin "3") (pinfunction "3_3") (pintype "passive"))
      (node (ref "T3") (pin "4") (pinfunction "4_4") (pintype "passive"))
      (node (ref "T3") (pin "5") (pinfunction "5_5") (pintype "passive"))
      (node (ref "T3") (pin "6") (pinfunction "6_6") (pintype "passive"))
    )
    (net (code "43") (name "Net-(T4-Pad1)") (class "Default")
      (node (ref "T4") (pin "1") (pinfunction "1_1") (pintype "passive"))
      (node (ref "T4") (pin "2") (pinfunction "2_2") (pintype "passive"))
      (node (ref "T4") (pin "3") (pinfunction "3_3") (pintype "passive"))
      (node (ref "T4") (pin "4") (pinfunction "4_4") (pintype "passive"))
      (node (ref "T4") (pin "5") (pinfunction "5_5") (pintype "passive"))
      (node (ref "T4") (pin "6") (pinfunction "6_6") (pintype "passive"))
    )
    (net (code "44") (name "Net-(T5-Pad1)") (class "Default")
      (node (ref "T5") (pin "1") (pinfunction "1_1") (pintype "passive"))
      (node (ref "T5") (pin "2") (pinfunction "2_2") (pintype "passive"))
      (node (ref "T5") (pin "3") (pinfunction "3_3") (pintype "passive"))
      (node (ref "T5") (pin "4") (pinfunction "4_4") (pintype "passive"))
      (node (ref "T5") (pin "5") (pinfunction "5_5") (pintype "passive"))
      (node (ref "T5") (pin "6") (pinfunction "6_6") (pintype "passive"))
    )
    (net (code "45") (name "Net-(T6-Pad1)") (class "Default")
      (node (ref "T6") (pin "1") (pinfunction "1_1") (pintype "passive"))
      (node (ref "T6") (pin "2") (pinfunction "2_2") (pintype "passive"))
      (node (ref "T6") (pin "3") (pinfunction "3_3") (pintype "passive"))
      (node (ref "T6") (pin "4") (pinfunction "4_4") (pintype "passive"))
      (node (ref "T6") (pin "5") (pinfunction "5_5") (pintype "passive"))
      (node (ref "T6") (pin "6") (pinfunction "6_6") (pintype "passive"))
    )
    (net (code "46") (name "Net-(T7-Pad1)") (class "Default")
      (node (ref "T7") (pin "1") (pinfunction "1_1") (pintype "passive"))
      (node (ref "T7") (pin "2") (pinfunction "2_2") (pintype "passive"))
      (node (ref "T7") (pin "3") (pinfunction "3_3") (pintype "passive"))
      (node (ref "T7") (pin "4") (pinfunction "4_4") (pintype "passive"))
      (node (ref "T7") (pin "5") (pinfunction "5_5") (pintype "passive"))
      (node (ref "T7") (pin "6") (pinfunction "6_6") (pintype "passive"))
    )
    (net (code "47") (name "Net-(T8-Pad1)") (class "Default")
      (node (ref "T8") (pin "1") (pinfunction "1_1") (pintype "passive"))
      (node (ref "T8") (pin "2") (pinfunction "2_2") (pintype "passive"))
      (node (ref "T8") (pin "3") (pinfunction "3_3") (pintype "passive"))
      (node (ref "T8") (pin "4") (pinfunction "4_4") (pintype "passive"))
      (node (ref "T8") (pin "5") (pinfunction "5_5") (pintype "passive"))
      (node (ref "T8") (pin "6") (pinfunction "6_6") (pintype "passive"))
    )
    (net (code "48") (name "Net-(T9-Pad1)") (class "Default")
      (node (ref "T9") (pin "1") (pinfunction "1_1") (pintype "passive"))
      (node (ref "T9") (pin "2") (pinfunction "2_2") (pintype "passive"))
      (node (ref "T9") (pin "3") (pinfunction "3_3") (pintype "passive"))
      (node (ref "T9") (pin "4") (pinfunction "4_4") (pintype "passive"))
      (node (ref "T9") (pin "5") (pinfunction "5_5") (pintype "passive"))
      (node (ref "T9") (pin "6") (pinfunction "6_6") (pintype "passive"))
    )
    (net (code "49") (name "Net-(T10-Pad1)") (class "Default")
      (node (ref "T10") (pin "1") (pinfunction "1_1") (pintype "passive"))
      (node (ref "T10") (pin "2") (pinfunction "2_2") (pintype "passive"))
      (node (ref "T10") (pin "3") (pinfunction "3_3") (pintype "passive"))
      (node (ref "T10") (pin "4") (pinfunction "4_4") (pintype "passive"))
      (node (ref "T10") (pin "5") (pinfunction "5_5") (pintype "passive"))
      (node (ref "T10") (pin "6") (pinfunction "6_6") (pintype "passive"))
    )
    (net (code "50") (name "Net-(T11-Pad1)") (class "Default")
      (node (ref "T11") (pin "1") (pinfunction "1_1") (pintype "passive"))
      (node (ref "T11") (pin "2") (pinfunction "2_2") (pintype "passive"))
      (node (ref "T11") (pin "3") (pinfunction "3_3") (pintype "passive"))
      (node (ref "T11") (pin "4") (pinfunction "4_4") (pintype "passive"))
      (node (ref "T11") (pin "5") (pinfunction "5_5") (pintype "passive"))
      (node (ref "T11") (pin "6") (pinfunction "6_6") (pintype "passive"))
    )
    (net (code "51") (name "Net-(T12-Pad1)") (class "Default")
      (node (ref "T12") (pin "1") (pinfunction "1_1") (pintype "passive"))
      (node (ref "T12") (pin "2") (pinfunction "2_2") (pintype "passive"))
      (node (ref "T12") (pin "3") (pinfunction "3_3") (pintype "passive"))
      (node (ref "T12") (pin "4") (pinfunction "4_4") (pintype "passive"))
      (node (ref "T12") (pin "5") (pinfunction "5_5") (pintype "passive"))
      (node (ref "T12") (pin "6") (pinfunction "6_6") (pintype "passive"))
    )
    (net (code "52") (name "Net-(T13-Pad1)") (class "Default")
      (node (ref "T13") (pin "1") (pinfunction "1_1") (pintype "passive"))
      (node (ref "T13") (pin "2") (pinfunction "2_2") (pintype "passive"))
      (node (ref "T13") (pin "3") (pinfunction "3_3") (pintype "passive"))
      (node (ref "T13") (pin "4") (pinfunction "4_4") (pintype "passive"))
      (node (ref "T13") (pin "5") (pinfunction "5_5") (pintype "passive"))
      (node (ref "T13") (pin "6") (pinfunction "6_6") (pintype "passive"))
    )
    (net (code "53") (name "Net-(T14-Pad1)") (class "Default")
      (node (ref "T14") (pin "1") (pinfunction "1_1") (pintype "passive"))
      (node (ref "T14") (pin "2") (pinfunction "2_2") (pintype "passive"))
      (node (ref "T14") (pin "3") (pinfunction "3_3") (pintype "passive"))
      (node (ref "T14") (pin "4") (pinfunction "4_4") (pintype "passive"))
      (node (ref "T14") (pin "5") (pinfunction "5_5") (pintype "passive"))
      (node (ref "T14") (pin "6") (pinfunction "6_6") (pintype "passive"))
    )
    (net (code "54") (name "Net-(T15-Pad1)") (class "Default")
      (node (ref "T15") (pin "1") (pinfunction "1_1") (pintype "passive"))
      (node (ref "T15") (pin "2") (pinfunction "2_2") (pintype "passive"))
      (node (ref "T15") (pin "3") (pinfunction "3_3") (pintype "passive"))
      (node (ref "T15") (pin "4") (pinfunction "4_4") (pintype "passive"))
      (node (ref "T15") (pin "5") (pinfunction "5_5") (pintype "passive"))
      (node (ref "T15") (pin "6") (pinfunction "6_6") (pintype "passive"))
    )
    (net (code "55") (name "Net-(T16-Pad1)") (class "Default")
      (node (ref "T16") (pin "1") (pinfunction "1_1") (pintype "passive"))
      (node (ref "T16") (pin "2") (pinfunction "2_2") (pintype "passive"))
      (node (ref "T16") (pin "3") (pinfunction "3_3") (pintype "passive"))
      (node (ref "T16") (pin "4") (pinfunction "4_4") (pintype "passive"))
      (node (ref "T16") (pin "5") (pinfunction "5_5") (pintype "passive"))
      (node (ref "T16") (pin "6") (pinfunction "6_6") (pintype "passive"))
    )
    (net (code "56") (name "Net-(T17-Pad1)") (class "Default")
      (node (ref "T17") (pin "1") (pinfunction "1_1") (pintype "passive"))
      (node (ref "T17") (pin "2") (pinfunction "2_2") (pintype "passive"))
      (node (ref "T17") (pin "3") (pinfunction "3_3") (pintype "passive"))
      (node (ref "T17") (pin "4") (pinfunction "4_4") (pintype "passive"))
      (node (ref "T17") (pin "5") (pinfunction "5_5") (pintype "passive"))
      (node (ref "T17") (pin "6") (pinfunction "6_6") (pintype "passive"))
    )
    (net (code "57") (name "Net-(T18-Pad1)") (class "Default")
      (node (ref "T18") (pin "1") (pinfunction "1_1") (pintype "passive"))
      (node (ref "T18") (pin "2") (pinfunction "2_2") (pintype "passive"))
      (node (ref "T18") (pin "3") (pinfunction "3_3") (pintype "passive"))
      (node (ref "T18") (pin "4") (pinfunction "4_4") (pintype "passive"))
      (node (ref "T18") (pin "5") (pinfunction "5_5") (pintype "passive"))
      (node (ref "T18") (pin "6") (pinfunction "6_6") (pintype "passive"))
    )
    (net (code "58") (name "Net-(T19-Pad1)") (class "Default")
      (node (ref "T19") (pin "1") (pinfunction "1_1") (pintype "passive"))
      (node (ref "T19") (pin "2") (pinfunction "2_2") (pintype "passive"))
      (node (ref "T19") (pin "3") (pinfunction "3_3") (pintype "passive"))
      (node (ref "T19") (pin "4") (pinfunction "4_4") (pintype "passive"))
      (node (ref "T19") (pin "5") (pinfunction "5_5") (pintype "passive"))
      (node (ref "T19") (pin "6") (pinfunction "6_6") (pintype "passive"))
    )
    (net (code "59") (name "Net-(T20-Pad1)") (class "Default")
      (node (ref "T20") (pin "1") (pinfunction "1_1") (pintype "passive"))
      (node (ref "T20") (pin "2") (pinfunction "2_2") (pintype "passive"))
      (node (ref "T20") (pin "3") (pinfunction "3_3") (pintype "passive"))
      (node (ref "T20") (pin "4") (pinfunction "4_4") (pintype "passive"))
      (node (ref "T20") (pin "5") (pinfunction "5_5") (pintype "passive"))
      (node (ref "T20") (pin "6") (pinfunction "6_6") (pintype "passive"))
    )
    (net (code "60") (name "Net-(T21-Pad1)") (class "Default")
      (node (ref "T21") (pin "1") (pinfunction "1_1") (pintype "passive"))
      (node (ref "T21") (pin "2") (pinfunction "2_2") (pintype "passive"))
      (node (ref "T21") (pin "3") (pinfunction "3_3") (pintype "passive"))
      (node (ref "T21") (pin "4") (pinfunction "4_4") (pintype "passive"))
      (node (ref "T21") (pin "5") (pinfunction "5_5") (pintype "passive"))
      (node (ref "T21") (pin "6") (pinfunction "6_6") (pintype "passive"))
    )
    (net (code "61") (name "Net-(T22-Pad1)") (class "Default")
      (node (ref "T22") (pin "1") (pinfunction "1_1") (pintype "passive"))
      (node (ref "T22") (pin "2") (pinfunction "2_2") (pintype "passive"))
      (node (ref "T22") (pin "3") (pinfunction "3_3") (pintype "passive"))
      (node (ref "T22") (pin "4") (pinfunction "4_4") (pintype "passive"))
      (node (ref "T22") (pin "5") (pinfunction "5_5") (pintype "passive"))
      (node (ref "T22") (pin "6") (pinfunction "6_6") (pintype "passive"))
    )
    (net (code "62") (name "Net-(T23-Pad1)") (class "Default")
      (node (ref "T23") (pin "1") (pinfunction "1_1") (pintype "passive"))
      (node (ref "T23") (pin "2") (pinfunction "2_2") (pintype "passive"))
      (node (ref "T23") (pin "3") (pinfunction "3_3") (pintype "passive"))
      (node (ref "T23") (pin "4") (pinfunction "4_4") (pintype "passive"))
      (node (ref "T23") (pin "5") (pinfunction "5_5") (pintype "passive"))
      (node (ref "T23") (pin "6") (pinfunction "6_6") (pintype "passive"))
    )
    (net (code "63") (name "Net-(T24-Pad1)") (class "Default")
      (node (ref "T24") (pin "1") (pinfunction "1_1") (pintype "passive"))
      (node (ref "T24") (pin "2") (pinfunction "2_2") (pintype "passive"))
      (node (ref "T24") (pin "3") (pinfunction "3_3") (pintype "passive"))
      (node (ref "T24") (pin "4") (pinfunction "4_4") (pintype "passive"))
      (node (ref "T24") (pin "5") (pinfunction "5_5") (pintype "passive"))
      (node (ref "T24") (pin "6") (pinfunction "6_6") (pintype "passive"))
    )
    (net (code "64") (name "Net-(T25-Pad1)") (class "Default")
      (node (ref "T25") (pin "1") (pinfunction "1_1") (pintype "passive"))
      (node (ref "T25") (pin "2") (pinfunction "2_2") (pintype "passive"))
      (node (ref "T25") (pin "3") (pinfunction "3_3") (pintype "passive"))
      (node (ref "T25") (pin "4") (pinfunction "4_4") (pintype "passive"))
      (node (ref "T25") (pin "5") (pinfunction "5_5") (pintype "passive"))
      (node (ref "T25") (pin "6") (pinfunction "6_6") (pintype "passive"))
    )
    (net (code "65") (name "Net-(T26-Pad1)") (class "Default")
      (node (ref "T26") (pin "1") (pinfunction "1_1") (pintype "passive"))
      (node (ref "T26") (pin "2") (pinfunction "2_2") (pintype "passive"))
      (node (ref "T26") (pin "3") (pinfunction "3_3") (pintype "passive"))
      (node (ref "T26") (pin "4") (pinfunction "4_4") (pintype "passive"))
      (node (ref "T26") (pin "5") (pinfunction "5_5") (pintype "passive"))
      (node (ref "T26") (pin "6") (pinfunction "6_6") (pintype "passive"))
    )
    (net (code "66") (name "Net-(T27-Pad1)") (class "Default")
      (node (ref "T27") (pin "1") (pinfunction "1_1") (pintype "passive"))
      (node (ref "T27") (pin "2") (pinfunction "2_2") (pintype "passive"))
      (node (ref "T27") (pin "3") (pinfunction "3_3") (pintype "passive"))
      (node (ref "T27") (pin "4") (pinfunction "4_4") (pintype "passive"))
      (node (ref "T27") (pin "5") (pinfunction "5_5") (pintype "passive"))
      (node (ref "T27") (pin "6") (pinfunction "6_6") (pintype "passive"))
    )
    (net (code "67") (name "Net-(T28-Pad1)") (class "Default")
      (node (ref "T28") (pin "1") (pinfunction "1_1") (pintype "passive"))
      (node (ref "T28") (pin "2") (pinfunction "2_2") (pintype "passive"))
      (node (ref "T28") (pin "3") (pinfunction "3_3") (pintype "passive"))
      (node (ref "T28") (pin "4") (pinfunction "4_4") (pintype "passive"))
      (node (ref "T28") (pin "5") (pinfunction "5_5") (pintype "passive"))
      (node (ref "T28") (pin "6") (pinfunction "6_6") (pintype "passive"))
    )
    (net (code "68") (name "Net-(T29-Pad1)") (class "Default")
      (node (ref "T29") (pin "1") (pinfunction "1_1") (pintype "passive"))
      (node (ref "T29") (pin "2") (pinfunction "2_2") (pintype "passive"))
      (node (ref "T29") (pin "3") (pinfunction "3_3") (pintype "passive"))
      (node (ref "T29") (pin "4") (pinfunction "4_4") (pintype "passive"))
      (node (ref "T29") (pin "5") (pinfunction "5_5") (pintype "passive"))
      (node (ref "T29") (pin "6") (pinfunction "6_6") (pintype "passive"))
    )
    (net (code "69") (name "Net-(T30-Pad1)") (class "Default")
      (node (ref "T30") (pin "1") (pinfunction "1_1") (pintype "passive"))
      (node (ref "T30") (pin "2") (pinfunction "2_2") (pintype "passive"))
      (node (ref "T30") (pin "3") (pinfunction "3_3") (pintype "passive"))
      (node (ref "T30") (pin "4") (pinfunction "4_4") (pintype "passive"))
      (node (ref "T30") (pin "5") (pinfunction "5_5") (pintype "passive"))
      (node (ref "T30") (pin "6") (pinfunction "6_6") (pintype "passive"))
    )
    (net (code "70") (name "Net-(T31-Pad1)") (class "Default")
      (node (ref "T31") (pin "1") (pinfunction "1_1") (pintype "passive"))
      (node (ref "T31") (pin "2") (pinfunction "2_2") (pintype "passive"))
      (node (ref "T31") (pin "3") (pinfunction "3_3") (pintype "passive"))
      (node (ref "T31") (pin "4") (pinfunction "4_4") (pintype "passive"))
      (node (ref "T31") (pin "5") (pinfunction "5_5") (pintype "passive"))
      (node (ref "T31") (pin "6") (pinfunction "6_6") (pintype "passive"))
    )
    (net (code "71") (name "Net-(T32-Pad1)") (class "Default")
      (node (ref "T32") (pin "1") (pinfunction "1_1") (pintype "passive"))
      (node (ref "T32") (pin "2") (pinfunction "2_2") (pintype "passive"))
      (node (ref "T32") (pin "3") (pinfunction "3_3") (pintype "passive"))
      (node (ref "T32") (pin "4") (pinfunction "4_4") (pintype "passive"))
      (node (ref "T32") (pin "5") (pinfunction "5_5") (pintype "passive"))
      (node (ref "T32") (pin "6") (pinfunction "6_6") (pintype "passive"))
    )
    (net (code "72") (name "Net-(T33-Pad1)") (class "Default")
      (node (ref "T33") (pin "1") (pinfunction "1_1") (pintype "passive"))
      (node (ref "T33") (pin "2") (pinfunction "2_2") (pintype "passive"))
      (node (ref "T33") (pin "3") (pinfunction "3_3") (pintype "passive"))
      (node (ref "T33") (pin "4") (pinfunction "4_4") (pintype "passive"))
      (node (ref "T33") (pin "5") (pinfunction "5_5") (pintype "passive"))
      (node (ref "T33") (pin "6") (pinfunction "6_6") (pintype "passive"))
    )
    (net (code "73") (name "Net-(T34-Pad1)") (class "Default")
      (node (ref "T34") (pin "1") (pinfunction "1_1") (pintype "passive"))
      (node (ref "T34") (pin "2") (pinfunction "2_2") (pintype "passive"))
      (node (ref "T34") (pin "3") (pinfunction "3_3") (pintype "passive"))
      (node (ref "T34") (pin "4") (pinfunction "4_4") (pintype "passive"))
      (node (ref "T34") (pin "5") (pinfunction "5_5") (pintype "passive"))
      (node (ref "T34") (pin "6") (pinfunction "6_6") (pintype "passive"))
    )
    (net (code "74") (name "Net-(T35-Pad1)") (class "Default")
      (node (ref "T35") (pin "1") (pinfunction "1_1") (pintype "passive"))
      (node (ref "T35") (pin "2") (pinfunction "2_2") (pintype "passive"))
      (node (ref "T35") (pin "3") (pinfunction "3_3") (pintype "passive"))
      (node (ref "T35") (pin "4") (pinfunction "4_4") (pintype "passive"))
      (node (ref "T35") (pin "5") (pinfunction "5_5") (pintype "passive"))
      (node (ref "T35") (pin "6") (pinfunction "6_6") (pintype "passive"))
    )
    (net (code "75") (name "Net-(T36-Pad1)") (class "Default")
      (node (ref "T36") (pin "1") (pinfunction "1_1") (pintype "passive"))
      (node (ref "T36") (pin "2") (pinfunction "2_2") (pintype "passive"))
      (node (ref "T36") (pin "3") (pinfunction "3_3") (pintype "passive"))
      (node (ref "T36") (pin "4") (pinfunction "4_4") (pintype "passive"))
      (node (ref "T36") (pin "5") (pinfunction "5_5") (pintype "passive"))
      (node (ref "T36") (pin "6") (pinfunction "6_6") (pintype "passive"))
    )
    (net (code "76") (name "Net-(T37-Pad1)") (class "Default")
      (node (ref "T37") (pin "1") (pinfunction "1_1") (pintype "passive"))
      (node (ref "T37") (pin "2") (pinfunction "2_2") (pintype "passive"))
      (node (ref "T37") (pin "3") (pinfunction "3_3") (pintype "passive"))
      (node (ref "T37") (pin "4") (pinfunction "4_4") (pintype "passive"))
      (node (ref "T37") (pin "5") (pinfunction "5_5") (pintype "passive"))
      (node (ref "T37") (pin "6") (pinfunction "6_6") (pintype "passive"))
    )
    (net (code "77") (name "Net-(T38-Pad1)") (class "Default")
      (node (ref "T38") (pin "1") (pinfunction "1_1") (pintype "passive"))
      (node (ref "T38") (pin "2") (pinfunction "2_2") (pintype "passive"))
      (node (ref "T38") (pin "3") (pinfunction "3_3") (pintype "passive"))
      (node (ref "T38") (pin "4") (pinfunction "4_4") (pintype "passive"))
      (node (ref "T38") (pin "5") (pinfunction "5_5") (pintype "passive"))
      (node (ref "T38") (pin "6") (pinfunction "6_6") (pintype "passive"))
    )
    (net (code "78") (name "VCC") (class "Default")
      (node (ref "P1") (pin "1") (pinfunction "1_1") (pintype "passive"))
      (node (ref "P1") (pin "10") (pinfunction "10_10") (pintype "passive"))
      (node (ref "P1") (pin "11") (pinfunction "11_11") (pintype "passive"))
      (node (ref "P1") (pin "12") (pinfunction "12_12") (pintype "passive"))
      (node (ref "P1") (pin "13") (pinfunction "13_13") (pintype "passive"))
      (node (ref "P1") (pin "14") (pinfunction "14_14") (pintype "passive"))
      (node (ref "P1") (pin "15") (pinfunction "15_15") (pintype "passive"))
      (node (ref "P1") (pin "16") (pinfunction "16_16") (pintype "passive"))
      (node (ref "P1") (pin "17") (pinfunction "17_17") (pintype "passive"))
      (node (ref "P1") (pin "18") (pinfunction "18_18") (pintype "passive"))
      (node (ref "P1") (pin "19") (pinfunction "19_19") (pintype "passive"))
      (node (ref "P1") (pin "2") (pinfunction "2_2") (pintype "passive"))
      (node (ref "P1") (pin "20") (pinfunction "20_20") (pintype "passive"))
      (node (ref "P1") (pin "21") (pinfunction "21_21") (pintype "passive"))
      (node (ref "P1") (pin "22") (pinfunction "22_22") (pintype "passive"))
      (node (ref "P1") (pin "23") (pinfunction "23_23") (pintype "passive"))
      (node (ref "P1") (pin "24") (pinfunction "24_24") (pintype "passive"))
      (node (ref "P1") (pin "25") (pinfunction "25_25") (pintype "passive"))
      (node (ref "P1") (pin "26") (pinfunction "26_26") (pintype "passive"))
      (node (ref "P1") (pin "27") (pinfunction "27_27") (pintype "passive"))
      (node (ref "P1") (pin "28") (pinfunction "28_28") (pintype "passive"))
      (node (ref "P1") (pin "29") (pinfunction "29_29") (pintype "passive"))
      (node (ref "P1") (pin "3") (pinfunction "3_3") (pintype "passive"))
      (node (ref "P1") (pin "30") (pinfunction "30_30") (pintype "passive"))
      (node (ref "P1") (pin "31") (pinfunction "31_31") (pintype "passive"))
      (node (ref "P1") (pin "32") (pinfunction "32_32") (pintype "passive"))
      (node (ref "P1") (pin "33") (pinfunction "33_33") (pintype "passive"))
      (node (ref "P1") (pin "34") (pinfunction "34_34") (pintype "passive"))
      (node (ref "P1") (pin "35") (pinfunction "35_35") (pintype "passive"))
      (node (ref "P1") (pin "36") (pinfunction "36_36") (pintype "passive"))
      (node (ref "P1") (pin "37") (pinfunction "37_37") (pintype "passive"))
      (node (ref "P1") (pin "38") (pinfunction "38_38") (pintype "passive"))
      (node (ref "P1") (pin "4") (pinfunction "4_4") (pintype "passive"))
      (node (ref "P1") (pin "5") (pinfunction "5_5") (pintype "passive"))
      (node (ref "P1") (pin "6") (pinfunction "6_6") (pintype "passive"))
      (node (ref "P1") (pin "7") (pinfunction "7_7") (pintype "passive"))
      (node (ref "P1") (pin "8") (pinfunction "8_8") (pintype "passive"))
      (node (ref "P1") (pin "9") (pinfunction "9_9") (pintype "passive"))
      (node (ref "P2") (pin "1") (pinfunction "1_1") (pintype "passive"))
      (node (ref "P2") (pin "10") (pinfunction "10_10") (pintype "passive"))
      (node (ref "P2") (pin "11") (pinfunction "11_11") (pintype "passive"))
      (node (ref "P2") (pin "12") (pinfunction "12_12") (pintype "passive"))
      (node (ref "P2") (pin "13") (pinfunction "13_13") (pintype "passive"))
      (node (ref "P2") (pin "14") (pinfunction "14_14") (pintype "passive"))
      (node (ref "P2") (pin "15") (pinfunction "15_15") (pintype "passive"))
      (node (ref "P2") (pin "16") (pinfunction "16_16") (pintype "passive"))
      (node (ref "P2") (pin "17") (pinfunction "17_17") (pintype "passive"))
      (node (ref "P2") (pin "18") (pinfunction "18_18") (pintype "passive"))
      (node (ref "P2") (pin "19") (pinfunction "19_19") (pintype "passive"))
      (node (ref "P2") (pin "2") (pinfunction "2_2") (pintype "passive"))
      (node (ref "P2") (pin "20") (pinfunction "20_20") (pintype "passive"))
      (node (ref "P2") (pin "21") (pinfunction "21_21") (pintype "passive"))
      (node (ref "P2") (pin "22") (pinfunction "22_22") (pintype "passive"))
      (node (ref "P2") (pin "23") (pinfunction "23_23") (pintype "passive"))
      (node (ref "P2") (pin "24") (pinfunction "24_24") (pintype "passive"))
      (node (ref "P2") (pin "25") (pinfunction "25_25") (pintype "passive"))
      (node (ref "P2") (pin "26") (pinfunction "26_26") (pintype "passive"))
      (node (ref "P2") (pin "27") (pinfunction "27_27") (pintype "passive"))
      (node (ref "P2") (pin "28") (pinfunction "28_28") (pintype "passive"))
      (node (ref "P2") (pin "29") (pinfunction "29_29") (pintype "passive"))
      (node (ref "P2") (pin "3") (pinfunction "3_3") (pintype "passive"))
      (node (ref "P2") (pin "30") (pinfunction "30_30") (pintype "passive"))
      (node (ref "P2") (pin "31") (pinfunction "31_31") (pintype "passive"))
      (node (ref "P2") (pin "32") (pinfunction "32_32") (pintype "passive"))
      (node (ref "P2") (pin "33") (pinfunction "33_33") (pintype "passive"))
      (node (ref "P2") (pin "34") (pinfunction "34_34") (pintype "passive"))
      (node (ref "P2") (pin "35") (pinfunction "35_35") (pintype "passive"))
      (node (ref "P2") (pin "36") (pinfunction "36_36") (pintype "passive"))
      (node (ref "P2") (pin "37") (pinfunction "37_37") (pintype "passive"))
      (node (ref "P2") (pin "38") (pinfunction "38_38") (pintype "passive"))
      (node (ref "P2") (pin "4") (pinfunction "4_4") (pintype "passive"))
      (node (ref "P2") (pin "5") (pinfunction "5_5") (pintype "passive"))
      (node (ref "P2") (pin "6") (pinfunction "6_6") (pintype "passive"))
      (node (ref "P2") (pin "7") (pinfunction "7_7") (pintype "passive"))
      (node (ref "P2") (pin "8") (pinfunction "8_8") (pintype "passive"))
      (node (ref "P2") (pin "9") (pinfunction "9_9") (pintype "passive"))
    )
  )
)
